# DualPowerSupply.net
KiCad netlist of a schematic drawn in EAGLE
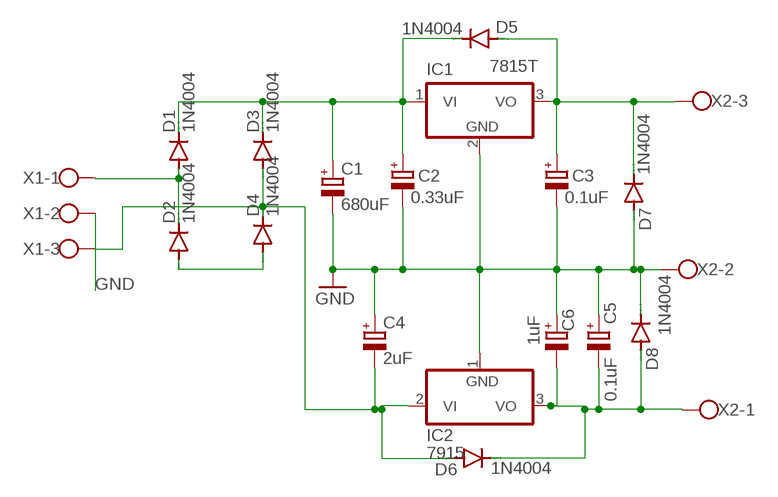
[diagram p0: schematic, sheet 1]

(export (version "E")
  (design (tool "Eeschema 10.0.6"))
  (components
    (comp (ref "C1")
      (value "680uF")
      (footprint "eagle-import:B45181B")
      (libsource (lib "eagle-import") (part "CPOL-EUB45181B"))
    )
    (comp (ref "C2")
      (value "0.33uF")
      (footprint "eagle-import:E2-4")
      (libsource (lib "eagle-import") (part "CPOL-EUE2-4"))
    )
    (comp (ref "C3")
      (value "0.1uF")
      (footprint "eagle-import:E2-4")
      (libsource (lib "eagle-import") (part "CPOL-EUE2-4"))
    )
    (comp (ref "C4")
      (value "2uF")
      (footprint "eagle-import:E2-4")
      (libsource (lib "eagle-import") (part "CPOL-EUE2-4"))
    )
    (comp (ref "C5")
      (value "0.1uF")
      (footprint "eagle-import:E2-4")
      (libsource (lib "eagle-import") (part "CPOL-EUE2-4"))
    )
    (comp (ref "C6")
      (value "1uF")
      (footprint "eagle-import:E2-4")
      (libsource (lib "eagle-import") (part "CPOL-EUE2-4"))
    )
    (comp (ref "D1")
      (value "1N4004")
      (footprint "eagle-import:DO41-10")
      (libsource (lib "eagle-import") (part "1N4004"))
    )
    (comp (ref "D2")
      (value "1N4004")
      (footprint "eagle-import:DO41-10")
      (libsource (lib "eagle-import") (part "1N4004"))
    )
    (comp (ref "D3")
      (value "1N4004")
      (footprint "eagle-import:DO41-10")
      (libsource (lib "eagle-import") (part "1N4004"))
    )
    (comp (ref "D4")
      (value "1N4004")
      (footprint "eagle-import:DO41-10")
      (libsource (lib "eagle-import") (part "1N4004"))
    )
    (comp (ref "D5")
      (value "1N4004")
      (footprint "eagle-import:DO41-10")
      (libsource (lib "eagle-import") (part "1N4004"))
    )
    (comp (ref "D6")
      (value "1N4004")
      (footprint "eagle-import:DO41-10")
      (libsource (lib "eagle-import") (part "1N4004"))
    )
    (comp (ref "D7")
      (value "1N4004")
      (footprint "eagle-import:DO41-10")
      (libsource (lib "eagle-import") (part "1N4004"))
    )
    (comp (ref "D8")
      (value "1N4004")
      (footprint "eagle-import:DO41-10")
      (libsource (lib "eagle-import") (part "1N4004"))
    )
    (comp (ref "IC1")
      (value "7815T")
      (footprint "eagle-import:TO220H")
      (libsource (lib "eagle-import") (part "78T15"))
    )
    (comp (ref "IC2")
      (value "7915")
      (footprint "eagle-import:TO220H")
      (libsource (lib "eagle-import") (part "79T15"))
    )
    (comp (ref "X1")
      (value "W237-103")
      (footprint "eagle-import:W237-103")
      (fields (field (name "MPN") "237-103"))
      (libsource (lib "eagle-import") (part "W237-103"))
    )
    (comp (ref "X2")
      (value "W237-103")
      (footprint "eagle-import:W237-103")
      (fields (field (name "MPN") "237-103"))
      (libsource (lib "eagle-import") (part "W237-103"))
    )
  )
  (nets
    (net (code "1") (name "GND") (class "Default")
      (node (ref "C1") (pin "-") (pinfunction "-_-") (pintype "passive"))
      (node (ref "C2") (pin "-") (pinfunction "-_-") (pintype "passive"))
      (node (ref "C3") (pin "-") (pinfunction "-_-") (pintype "passive"))
      (node (ref "C4") (pin "+") (pinfunction "+_+") (pintype "passive"))
      (node (ref "C5") (pin "+") (pinfunction "+_+") (pintype "passive"))
      (node (ref "C6") (pin "+") (pinfunction "+_+") (pintype "passive"))
      (node (ref "D7") (pin "A") (pinfunction "A_A") (pintype "passive"))
      (node (ref "D8") (pin "C") (pinfunction "C_C") (pintype "passive"))
      (node (ref "IC1") (pin "2") (pinfunction "GND_2") (pintype "passive"))
      (node (ref "IC2") (pin "1") (pinfunction "GND_1") (pintype "passive"))
      (node (ref "X1") (pin "2") (pinfunction "KL_2") (pintype "passive"))
      (node (ref "X2") (pin "2") (pinfunction "KL_2") (pintype "passive"))
    )
    (net (code "2") (name "Net-(D2-PadA)") (class "Default")
      (node (ref "D2") (pin "A") (pinfunction "A_A") (pintype "passive"))
      (node (ref "D4") (pin "A") (pinfunction "A_A") (pintype "passive"))
    )
    (net (code "3") (name "Net-(IC1-VI)") (class "Default")
      (node (ref "C1") (pin "+") (pinfunction "+_+") (pintype "passive"))
      (node (ref "C2") (pin "+") (pinfunction "+_+") (pintype "passive"))
      (node (ref "D1") (pin "C") (pinfunction "C_C") (pintype "passive"))
      (node (ref "D3") (pin "C") (pinfunction "C_C") (pintype "passive"))
      (node (ref "D5") (pin "C") (pinfunction "C_C") (pintype "passive"))
      (node (ref "IC1") (pin "1") (pinfunction "VI_1") (pintype "input"))
    )
    (net (code "4") (name "Net-(IC1-VO)") (class "Default")
      (node (ref "C3") (pin "+") (pinfunction "+_+") (pintype "passive"))
      (node (ref "D5") (pin "A") (pinfunction "A_A") (pintype "passive"))
      (node (ref "D7") (pin "C") (pinfunction "C_C") (pintype "passive"))
      (node (ref "IC1") (pin "3") (pinfunction "VO_3") (pintype "passive"))
      (node (ref "X2") (pin "3") (pinfunction "KL_3") (pintype "passive"))
    )
    (net (code "5") (name "Net-(IC2-VI)") (class "Default")
      (node (ref "C4") (pin "-") (pinfunction "-_-") (pintype "passive"))
      (node (ref "D3") (pin "A") (pinfunction "A_A") (pintype "passive"))
      (node (ref "D4") (pin "C") (pinfunction "C_C") (pintype "passive"))
      (node (ref "D6") (pin "A") (pinfunction "A_A") (pintype "passive"))
      (node (ref "IC2") (pin "2") (pinfunction "VI_2") (pintype "input"))
      (node (ref "X1") (pin "3") (pinfunction "KL_3") (pintype "passive"))
    )
    (net (code "6") (name "Net-(IC2-VO)") (class "Default")
      (node (ref "C5") (pin "-") (pinfunction "-_-") (pintype "passive"))
      (node (ref "C6") (pin "-") (pinfunction "-_-") (pintype "passive"))
      (node (ref "D6") (pin "C") (pinfunction "C_C") (pintype "passive"))
      (node (ref "D8") (pin "A") (pinfunction "A_A") (pintype "passive"))
      (node (ref "IC2") (pin "3") (pinfunction "VO_3") (pintype "passive"))
      (node (ref "X2") (pin "1") (pinfunction "KL_1") (pintype "passive"))
    )
    (net (code "7") (name "Net-(X1A-KL)") (class "Default")
      (node (ref "D1") (pin "A") (pinfunction "A_A") (pintype "passive"))
      (node (ref "D2") (pin "C") (pinfunction "C_C") (pintype "passive"))
      (node (ref "X1") (pin "1") (pinfunction "KL_1") (pintype "passive"))
    )
  )
)
